# hd6303-mb-ram-rom-x1.net
KiCad netlist of a schematic drawn in EAGLE
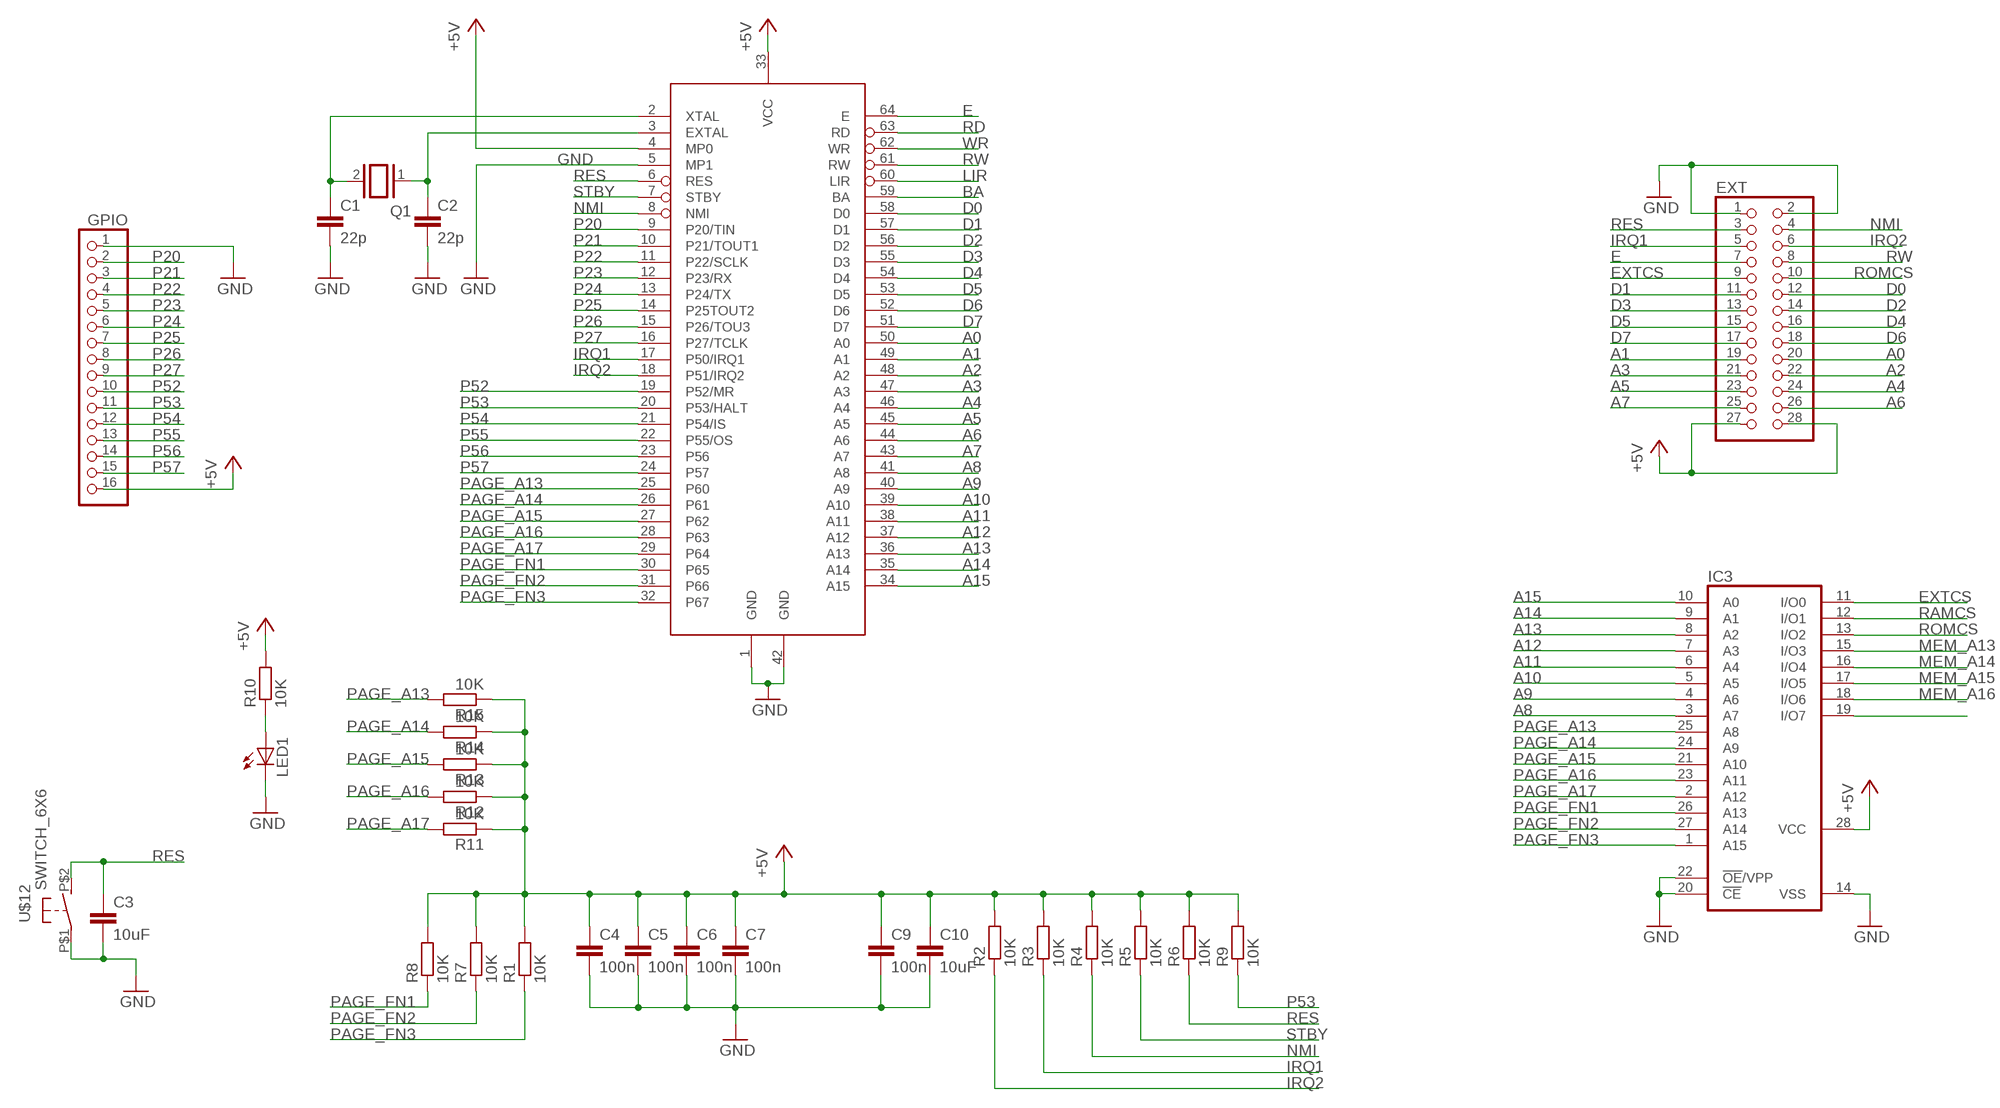
[diagram p0: schematic, sheet 1]
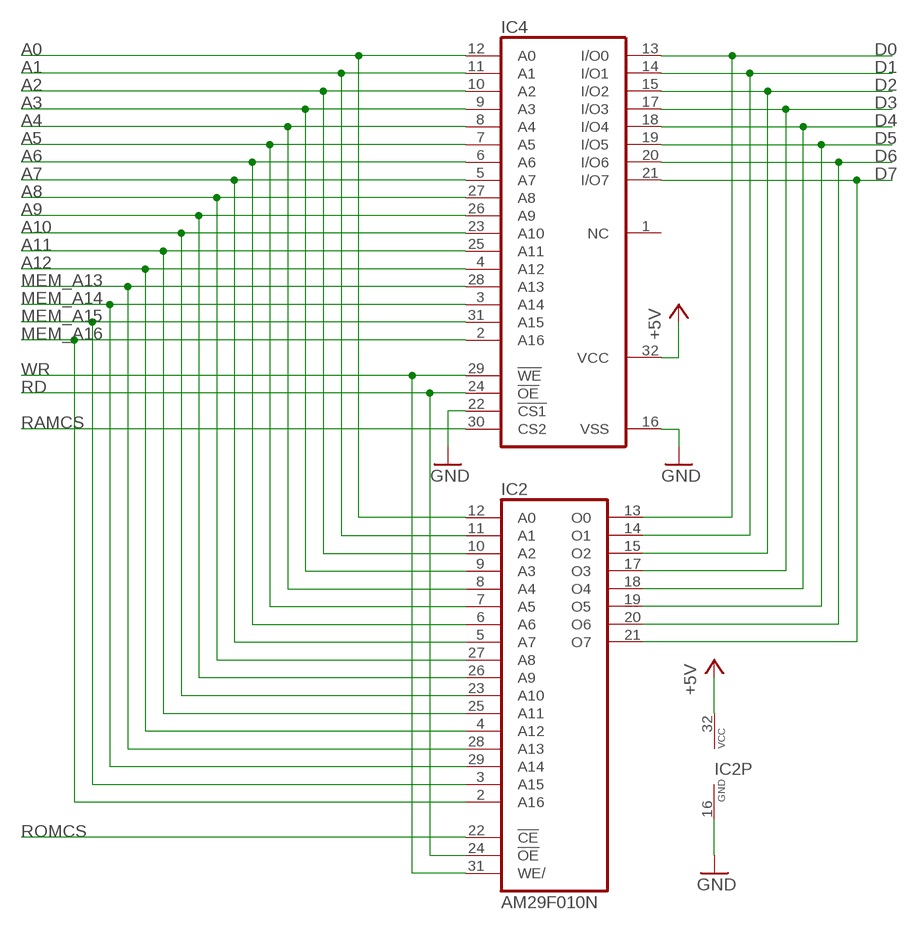
[diagram p1: schematic, sheet 2]

(export (version "E")
  (design (tool "Eeschema 10.0.6"))
  (components
    (comp (ref "C1")
      (value "22p")
      (footprint "eagle-import:C0603")
      (libsource (lib "eagle-import") (part "rcl_334_C-EUC0603"))
    )
    (comp (ref "C2")
      (value "22p")
      (footprint "eagle-import:C0603")
      (libsource (lib "eagle-import") (part "C-EUC0603"))
    )
    (comp (ref "C3")
      (value "10uF")
      (footprint "eagle-import:C0805")
      (libsource (lib "eagle-import") (part "resistor_348_C-EUC0805"))
    )
    (comp (ref "C4")
      (value "100n")
      (footprint "eagle-import:C0603")
      (libsource (lib "eagle-import") (part "C-EUC0603"))
    )
    (comp (ref "C5")
      (value "100n")
      (footprint "eagle-import:C0603")
      (libsource (lib "eagle-import") (part "C-EUC0603"))
    )
    (comp (ref "C6")
      (value "100n")
      (footprint "eagle-import:C0603")
      (libsource (lib "eagle-import") (part "C-EUC0603"))
    )
    (comp (ref "C7")
      (value "100n")
      (footprint "eagle-import:C0603")
      (libsource (lib "eagle-import") (part "C-EUC0603"))
    )
    (comp (ref "C9")
      (value "100n")
      (footprint "eagle-import:C0603")
      (libsource (lib "eagle-import") (part "C-EUC0603"))
    )
    (comp (ref "C10")
      (value "10uF")
      (footprint "eagle-import:C0805")
      (libsource (lib "eagle-import") (part "resistor_348_C-EUC0805"))
    )
    (comp (ref "EXT")
      (value "PINHD-2X14")
      (footprint "eagle-import:2X14")
      (libsource (lib "eagle-import") (part "PINHD-2X14"))
    )
    (comp (ref "GPIO")
      (value "PINHD-1X16")
      (footprint "eagle-import:1X16")
      (libsource (lib "eagle-import") (part "PINHD-1X16"))
    )
    (comp (ref "IC3")
      (value "27512G")
      (footprint "eagle-import:DIL28-6")
      (libsource (lib "eagle-import") (part "27512G"))
    )
    (comp (ref "LED1")
      (value "LED5MM")
      (footprint "eagle-import:LED5MM")
      (libsource (lib "eagle-import") (part "LED5MM"))
    )
    (comp (ref "Q1")
      (value "XTAL/S")
      (footprint "eagle-import:QS")
      (libsource (lib "eagle-import") (part "XTAL/S"))
    )
    (comp (ref "R1")
      (value "10K")
      (footprint "eagle-import:R0603")
      (libsource (lib "eagle-import") (part "R-EU_R0603"))
    )
    (comp (ref "R2")
      (value "10K")
      (footprint "eagle-import:R0603")
      (libsource (lib "eagle-import") (part "R-EU_R0603"))
    )
    (comp (ref "R3")
      (value "10K")
      (footprint "eagle-import:R0603")
      (libsource (lib "eagle-import") (part "R-EU_R0603"))
    )
    (comp (ref "R4")
      (value "10K")
      (footprint "eagle-import:R0603")
      (libsource (lib "eagle-import") (part "R-EU_R0603"))
    )
    (comp (ref "R5")
      (value "10K")
      (footprint "eagle-import:R0603")
      (libsource (lib "eagle-import") (part "R-EU_R0603"))
    )
    (comp (ref "R6")
      (value "10K")
      (footprint "eagle-import:R0603")
      (libsource (lib "eagle-import") (part "R-EU_R0603"))
    )
    (comp (ref "R7")
      (value "10K")
      (footprint "eagle-import:R0603")
      (libsource (lib "eagle-import") (part "R-EU_R0603"))
    )
    (comp (ref "R8")
      (value "10K")
      (footprint "eagle-import:R0603")
      (libsource (lib "eagle-import") (part "R-EU_R0603"))
    )
    (comp (ref "R9")
      (value "10K")
      (footprint "eagle-import:R0603")
      (libsource (lib "eagle-import") (part "R-EU_R0603"))
    )
    (comp (ref "R10")
      (value "10K")
      (footprint "eagle-import:R0603")
      (libsource (lib "eagle-import") (part "R-EU_R0603"))
    )
    (comp (ref "R11")
      (value "10K")
      (footprint "eagle-import:R0603")
      (libsource (lib "eagle-import") (part "R-EU_R0603"))
    )
    (comp (ref "R12")
      (value "10K")
      (footprint "eagle-import:R0603")
      (libsource (lib "eagle-import") (part "R-EU_R0603"))
    )
    (comp (ref "R13")
      (value "10K")
      (footprint "eagle-import:R0603")
      (libsource (lib "eagle-import") (part "R-EU_R0603"))
    )
    (comp (ref "R14")
      (value "10K")
      (footprint "eagle-import:R0603")
      (libsource (lib "eagle-import") (part "R-EU_R0603"))
    )
    (comp (ref "R15")
      (value "10K")
      (footprint "eagle-import:R0603")
      (libsource (lib "eagle-import") (part "R-EU_R0603"))
    )
    (comp (ref "U$1")
      (value "HD6303YCP")
      (footprint "eagle-import:DP-64S")
      (libsource (lib "eagle-import") (part "HD6303YCP"))
    )
    (comp (ref "U$12")
      (value "SWITCH_6X6")
      (footprint "eagle-import:SWITCH_6X6")
      (libsource (lib "eagle-import") (part "SWITCH_6X6"))
    )
    (comp (ref "IC2")
      (value "AM29F010N")
      (footprint "eagle-import:DIP32")
      (libsource (lib "eagle-import") (part "AM29F010N"))
    )
    (comp (ref "IC4")
      (value "628128P")
      (footprint "eagle-import:DIL32")
      (libsource (lib "eagle-import") (part "628128P"))
    )
  )
  (nets
    (net (code "1") (name "+5V") (class "Default")
      (node (ref "C10") (pin "1") (pinfunction "1_1") (pintype "passive"))
      (node (ref "C4") (pin "1") (pinfunction "1_1") (pintype "passive"))
      (node (ref "C5") (pin "1") (pinfunction "1_1") (pintype "passive"))
      (node (ref "C6") (pin "1") (pinfunction "1_1") (pintype "passive"))
      (node (ref "C7") (pin "1") (pinfunction "1_1") (pintype "passive"))
      (node (ref "C9") (pin "1") (pinfunction "1_1") (pintype "passive"))
      (node (ref "EXT") (pin "27") (pinfunction "27_27") (pintype "passive"))
      (node (ref "EXT") (pin "28") (pinfunction "28_28") (pintype "passive"))
      (node (ref "GPIO") (pin "16") (pinfunction "16_16") (pintype "passive"))
      (node (ref "IC2") (pin "32") (pinfunction "VCC_32") (pintype "power_in"))
      (node (ref "IC3") (pin "28") (pinfunction "VCC_28") (pintype "power_in"))
      (node (ref "IC4") (pin "32") (pinfunction "VCC_32") (pintype "power_in"))
      (node (ref "R1") (pin "2") (pinfunction "2_2") (pintype "passive"))
      (node (ref "R10") (pin "2") (pinfunction "2_2") (pintype "passive"))
      (node (ref "R11") (pin "1") (pinfunction "1_1") (pintype "passive"))
      (node (ref "R12") (pin "1") (pinfunction "1_1") (pintype "passive"))
      (node (ref "R13") (pin "1") (pinfunction "1_1") (pintype "passive"))
      (node (ref "R14") (pin "1") (pinfunction "1_1") (pintype "passive"))
      (node (ref "R15") (pin "1") (pinfunction "1_1") (pintype "passive"))
      (node (ref "R2") (pin "2") (pinfunction "2_2") (pintype "passive"))
      (node (ref "R3") (pin "2") (pinfunction "2_2") (pintype "passive"))
      (node (ref "R4") (pin "2") (pinfunction "2_2") (pintype "passive"))
      (node (ref "R5") (pin "2") (pinfunction "2_2") (pintype "passive"))
      (node (ref "R6") (pin "2") (pinfunction "2_2") (pintype "passive"))
      (node (ref "R7") (pin "2") (pinfunction "2_2") (pintype "passive"))
      (node (ref "R8") (pin "2") (pinfunction "2_2") (pintype "passive"))
      (node (ref "R9") (pin "2") (pinfunction "2_2") (pintype "passive"))
      (node (ref "U$1") (pin "33") (pinfunction "VCC_33") (pintype "power_in"))
      (node (ref "U$1") (pin "4") (pinfunction "MP0_4") (pintype "input"))
    )
    (net (code "2") (name "A0") (class "Default")
      (node (ref "EXT") (pin "20") (pinfunction "20_20") (pintype "passive"))
      (node (ref "IC2") (pin "12") (pinfunction "A0_12") (pintype "input"))
      (node (ref "IC4") (pin "12") (pinfunction "A0_12") (pintype "input"))
      (node (ref "U$1") (pin "50") (pinfunction "A0_50") (pintype "output"))
    )
    (net (code "3") (name "A1") (class "Default")
      (node (ref "EXT") (pin "19") (pinfunction "19_19") (pintype "passive"))
      (node (ref "IC2") (pin "11") (pinfunction "A1_11") (pintype "input"))
      (node (ref "IC4") (pin "11") (pinfunction "A1_11") (pintype "input"))
      (node (ref "U$1") (pin "49") (pinfunction "A1_49") (pintype "output"))
    )
    (net (code "4") (name "A2") (class "Default")
      (node (ref "EXT") (pin "22") (pinfunction "22_22") (pintype "passive"))
      (node (ref "IC2") (pin "10") (pinfunction "A2_10") (pintype "input"))
      (node (ref "IC4") (pin "10") (pinfunction "A2_10") (pintype "input"))
      (node (ref "U$1") (pin "48") (pinfunction "A2_48") (pintype "output"))
    )
    (net (code "5") (name "A3") (class "Default")
      (node (ref "EXT") (pin "21") (pinfunction "21_21") (pintype "passive"))
      (node (ref "IC2") (pin "9") (pinfunction "A3_9") (pintype "input"))
      (node (ref "IC4") (pin "9") (pinfunction "A3_9") (pintype "input"))
      (node (ref "U$1") (pin "47") (pinfunction "A3_47") (pintype "output"))
    )
    (net (code "6") (name "A4") (class "Default")
      (node (ref "EXT") (pin "24") (pinfunction "24_24") (pintype "passive"))
      (node (ref "IC2") (pin "8") (pinfunction "A4_8") (pintype "input"))
      (node (ref "IC4") (pin "8") (pinfunction "A4_8") (pintype "input"))
      (node (ref "U$1") (pin "46") (pinfunction "A4_46") (pintype "output"))
    )
    (net (code "7") (name "A5") (class "Default")
      (node (ref "EXT") (pin "23") (pinfunction "23_23") (pintype "passive"))
      (node (ref "IC2") (pin "7") (pinfunction "A5_7") (pintype "input"))
      (node (ref "IC4") (pin "7") (pinfunction "A5_7") (pintype "input"))
      (node (ref "U$1") (pin "45") (pinfunction "A5_45") (pintype "output"))
    )
    (net (code "8") (name "A6") (class "Default")
      (node (ref "EXT") (pin "26") (pinfunction "26_26") (pintype "passive"))
      (node (ref "IC2") (pin "6") (pinfunction "A6_6") (pintype "input"))
      (node (ref "IC4") (pin "6") (pinfunction "A6_6") (pintype "input"))
      (node (ref "U$1") (pin "44") (pinfunction "A6_44") (pintype "output"))
    )
    (net (code "9") (name "A7") (class "Default")
      (node (ref "EXT") (pin "25") (pinfunction "25_25") (pintype "passive"))
      (node (ref "IC2") (pin "5") (pinfunction "A7_5") (pintype "input"))
      (node (ref "IC4") (pin "5") (pinfunction "A7_5") (pintype "input"))
      (node (ref "U$1") (pin "43") (pinfunction "A7_43") (pintype "output"))
    )
    (net (code "10") (name "A8") (class "Default")
      (node (ref "IC2") (pin "27") (pinfunction "A8_27") (pintype "input"))
      (node (ref "IC3") (pin "3") (pinfunction "A7_3") (pintype "input"))
      (node (ref "IC4") (pin "27") (pinfunction "A8_27") (pintype "input"))
      (node (ref "U$1") (pin "41") (pinfunction "A8_41") (pintype "output"))
    )
    (net (code "11") (name "A9") (class "Default")
      (node (ref "IC2") (pin "26") (pinfunction "A9_26") (pintype "input"))
      (node (ref "IC3") (pin "4") (pinfunction "A6_4") (pintype "input"))
      (node (ref "IC4") (pin "26") (pinfunction "A9_26") (pintype "input"))
      (node (ref "U$1") (pin "40") (pinfunction "A9_40") (pintype "output"))
    )
    (net (code "12") (name "A10") (class "Default")
      (node (ref "IC2") (pin "23") (pinfunction "A10_23") (pintype "input"))
      (node (ref "IC3") (pin "5") (pinfunction "A5_5") (pintype "input"))
      (node (ref "IC4") (pin "23") (pinfunction "A10_23") (pintype "input"))
      (node (ref "U$1") (pin "39") (pinfunction "A10_39") (pintype "output"))
    )
    (net (code "13") (name "A11") (class "Default")
      (node (ref "IC2") (pin "25") (pinfunction "A11_25") (pintype "input"))
      (node (ref "IC3") (pin "6") (pinfunction "A4_6") (pintype "input"))
      (node (ref "IC4") (pin "25") (pinfunction "A11_25") (pintype "input"))
      (node (ref "U$1") (pin "38") (pinfunction "A11_38") (pintype "output"))
    )
    (net (code "14") (name "A12") (class "Default")
      (node (ref "IC2") (pin "4") (pinfunction "A12_4") (pintype "input"))
      (node (ref "IC3") (pin "7") (pinfunction "A3_7") (pintype "input"))
      (node (ref "IC4") (pin "4") (pinfunction "A12_4") (pintype "input"))
      (node (ref "U$1") (pin "37") (pinfunction "A12_37") (pintype "output"))
    )
    (net (code "15") (name "A13") (class "Default")
      (node (ref "IC3") (pin "8") (pinfunction "A2_8") (pintype "input"))
      (node (ref "U$1") (pin "36") (pinfunction "A13_36") (pintype "output"))
    )
    (net (code "16") (name "A14") (class "Default")
      (node (ref "IC3") (pin "9") (pinfunction "A1_9") (pintype "input"))
      (node (ref "U$1") (pin "35") (pinfunction "A14_35") (pintype "output"))
    )
    (net (code "17") (name "A15") (class "Default")
      (node (ref "IC3") (pin "10") (pinfunction "A0_10") (pintype "input"))
      (node (ref "U$1") (pin "34") (pinfunction "A15_34") (pintype "output"))
    )
    (net (code "18") (name "BA") (class "Default")
      (node (ref "U$1") (pin "59") (pinfunction "BA_59") (pintype "output"))
    )
    (net (code "19") (name "D0") (class "Default")
      (node (ref "EXT") (pin "12") (pinfunction "12_12") (pintype "passive"))
      (node (ref "IC2") (pin "13") (pinfunction "O0_13") (pintype "tri_state"))
      (node (ref "IC4") (pin "13") (pinfunction "I/O0_13") (pintype "bidirectional"))
      (node (ref "U$1") (pin "58") (pinfunction "D0_58") (pintype "bidirectional"))
    )
    (net (code "20") (name "D1") (class "Default")
      (node (ref "EXT") (pin "11") (pinfunction "11_11") (pintype "passive"))
      (node (ref "IC2") (pin "14") (pinfunction "O1_14") (pintype "tri_state"))
      (node (ref "IC4") (pin "14") (pinfunction "I/O1_14") (pintype "bidirectional"))
      (node (ref "U$1") (pin "57") (pinfunction "D1_57") (pintype "bidirectional"))
    )
    (net (code "21") (name "D2") (class "Default")
      (node (ref "EXT") (pin "14") (pinfunction "14_14") (pintype "passive"))
      (node (ref "IC2") (pin "15") (pinfunction "O2_15") (pintype "tri_state"))
      (node (ref "IC4") (pin "15") (pinfunction "I/O2_15") (pintype "bidirectional"))
      (node (ref "U$1") (pin "56") (pinfunction "D2_56") (pintype "bidirectional"))
    )
    (net (code "22") (name "D3") (class "Default")
      (node (ref "EXT") (pin "13") (pinfunction "13_13") (pintype "passive"))
      (node (ref "IC2") (pin "17") (pinfunction "O3_17") (pintype "tri_state"))
      (node (ref "IC4") (pin "17") (pinfunction "I/O3_17") (pintype "bidirectional"))
      (node (ref "U$1") (pin "55") (pinfunction "D3_55") (pintype "bidirectional"))
    )
    (net (code "23") (name "D4") (class "Default")
      (node (ref "EXT") (pin "16") (pinfunction "16_16") (pintype "passive"))
      (node (ref "IC2") (pin "18") (pinfunction "O4_18") (pintype "tri_state"))
      (node (ref "IC4") (pin "18") (pinfunction "I/O4_18") (pintype "bidirectional"))
      (node (ref "U$1") (pin "54") (pinfunction "D4_54") (pintype "bidirectional"))
    )
    (net (code "24") (name "D5") (class "Default")
      (node (ref "EXT") (pin "15") (pinfunction "15_15") (pintype "passive"))
      (node (ref "IC2") (pin "19") (pinfunction "O5_19") (pintype "tri_state"))
      (node (ref "IC4") (pin "19") (pinfunction "I/O5_19") (pintype "bidirectional"))
      (node (ref "U$1") (pin "53") (pinfunction "D5_53") (pintype "bidirectional"))
    )
    (net (code "25") (name "D6") (class "Default")
      (node (ref "EXT") (pin "18") (pinfunction "18_18") (pintype "passive"))
      (node (ref "IC2") (pin "20") (pinfunction "O6_20") (pintype "tri_state"))
      (node (ref "IC4") (pin "20") (pinfunction "I/O6_20") (pintype "bidirectional"))
      (node (ref "U$1") (pin "52") (pinfunction "D6_52") (pintype "bidirectional"))
    )
    (net (code "26") (name "D7") (class "Default")
      (node (ref "EXT") (pin "17") (pinfunction "17_17") (pintype "passive"))
      (node (ref "IC2") (pin "21") (pinfunction "O7_21") (pintype "tri_state"))
      (node (ref "IC4") (pin "21") (pinfunction "I/O7_21") (pintype "bidirectional"))
      (node (ref "U$1") (pin "51") (pinfunction "D7_51") (pintype "bidirectional"))
    )
    (net (code "27") (name "E") (class "Default")
      (node (ref "EXT") (pin "7") (pinfunction "7_7") (pintype "passive"))
      (node (ref "U$1") (pin "64") (pinfunction "E_64") (pintype "output"))
    )
    (net (code "28") (name "EXTCS") (class "Default")
      (node (ref "EXT") (pin "9") (pinfunction "9_9") (pintype "passive"))
      (node (ref "IC3") (pin "11") (pinfunction "I/O0_11") (pintype "tri_state"))
    )
    (net (code "29") (name "GND") (class "Default")
      (node (ref "C1") (pin "2") (pinfunction "2_2") (pintype "passive"))
      (node (ref "C10") (pin "2") (pinfunction "2_2") (pintype "passive"))
      (node (ref "C2") (pin "2") (pinfunction "2_2") (pintype "passive"))
      (node (ref "C3") (pin "2") (pinfunction "2_2") (pintype "passive"))
      (node (ref "C4") (pin "2") (pinfunction "2_2") (pintype "passive"))
      (node (ref "C5") (pin "2") (pinfunction "2_2") (pintype "passive"))
      (node (ref "C6") (pin "2") (pinfunction "2_2") (pintype "passive"))
      (node (ref "C7") (pin "2") (pinfunction "2_2") (pintype "passive"))
      (node (ref "C9") (pin "2") (pinfunction "2_2") (pintype "passive"))
      (node (ref "EXT") (pin "1") (pinfunction "1_1") (pintype "passive"))
      (node (ref "EXT") (pin "2") (pinfunction "2_2") (pintype "passive"))
      (node (ref "GPIO") (pin "1") (pinfunction "1_1") (pintype "passive"))
      (node (ref "IC2") (pin "16") (pinfunction "GND_16") (pintype "power_in"))
      (node (ref "IC3") (pin "14") (pinfunction "VSS_14") (pintype "power_in"))
      (node (ref "IC3") (pin "20") (pinfunction "~{CE}_20") (pintype "input"))
      (node (ref "IC3") (pin "22") (pinfunction "~{OE}/VPP_22") (pintype "input"))
      (node (ref "IC4") (pin "16") (pinfunction "VSS_16") (pintype "power_in"))
      (node (ref "IC4") (pin "22") (pinfunction "~{CS1}_22") (pintype "input"))
      (node (ref "LED1") (pin "K") (pinfunction "C_K") (pintype "passive"))
      (node (ref "U$1") (pin "1") (pinfunction "GND_1") (pintype "power_in"))
      (node (ref "U$1") (pin "42") (pinfunction "GND_42") (pintype "power_in"))
      (node (ref "U$1") (pin "5") (pinfunction "MP1_5") (pintype "input"))
      (node (ref "U$12") (pin "P$1") (pinfunction "P_P$1") (pintype "passive"))
    )
    (net (code "30") (name "IRQ1") (class "Default")
      (node (ref "EXT") (pin "5") (pinfunction "5_5") (pintype "passive"))
      (node (ref "R3") (pin "1") (pinfunction "1_1") (pintype "passive"))
      (node (ref "U$1") (pin "17") (pinfunction "P50/IRQ1_17") (pintype "bidirectional"))
    )
    (net (code "31") (name "IRQ2") (class "Default")
      (node (ref "EXT") (pin "6") (pinfunction "6_6") (pintype "passive"))
      (node (ref "R2") (pin "1") (pinfunction "1_1") (pintype "passive"))
      (node (ref "U$1") (pin "18") (pinfunction "P51/IRQ2_18") (pintype "bidirectional"))
    )
    (net (code "32") (name "LIR") (class "Default")
      (node (ref "U$1") (pin "60") (pinfunction "LIR_60") (pintype "output"))
    )
    (net (code "33") (name "MEM_A13") (class "Default")
      (node (ref "IC2") (pin "28") (pinfunction "A13_28") (pintype "input"))
      (node (ref "IC3") (pin "15") (pinfunction "I/O3_15") (pintype "tri_state"))
      (node (ref "IC4") (pin "28") (pinfunction "A13_28") (pintype "input"))
    )
    (net (code "34") (name "MEM_A14") (class "Default")
      (node (ref "IC2") (pin "29") (pinfunction "A14_29") (pintype "input"))
      (node (ref "IC3") (pin "16") (pinfunction "I/O4_16") (pintype "tri_state"))
      (node (ref "IC4") (pin "3") (pinfunction "A14_3") (pintype "input"))
    )
    (net (code "35") (name "MEM_A15") (class "Default")
      (node (ref "IC2") (pin "3") (pinfunction "A15_3") (pintype "input"))
      (node (ref "IC3") (pin "17") (pinfunction "I/O5_17") (pintype "tri_state"))
      (node (ref "IC4") (pin "31") (pinfunction "A15_31") (pintype "input"))
    )
    (net (code "36") (name "MEM_A16") (class "Default")
      (node (ref "IC2") (pin "2") (pinfunction "A16_2") (pintype "input"))
      (node (ref "IC3") (pin "18") (pinfunction "I/O6_18") (pintype "tri_state"))
      (node (ref "IC4") (pin "2") (pinfunction "A16_2") (pintype "input"))
    )
    (net (code "37") (name "NMI") (class "Default")
      (node (ref "EXT") (pin "4") (pinfunction "4_4") (pintype "passive"))
      (node (ref "R4") (pin "1") (pinfunction "1_1") (pintype "passive"))
      (node (ref "U$1") (pin "8") (pinfunction "NMI_8") (pintype "input"))
    )
    (net (code "38") (name "Net-(LED1-PadA)") (class "Default")
      (node (ref "LED1") (pin "A") (pinfunction "A_A") (pintype "passive"))
      (node (ref "R10") (pin "1") (pinfunction "1_1") (pintype "passive"))
    )
    (net (code "39") (name "Net-(U$1-EXTAL)") (class "Default")
      (node (ref "C2") (pin "1") (pinfunction "1_1") (pintype "passive"))
      (node (ref "Q1") (pin "1") (pinfunction "1_1") (pintype "passive"))
      (node (ref "U$1") (pin "3") (pinfunction "EXTAL_3") (pintype "input"))
    )
    (net (code "40") (name "Net-(U$1-XTAL)") (class "Default")
      (node (ref "C1") (pin "1") (pinfunction "1_1") (pintype "passive"))
      (node (ref "Q1") (pin "2") (pinfunction "2_2") (pintype "passive"))
      (node (ref "U$1") (pin "2") (pinfunction "XTAL_2") (pintype "input"))
    )
    (net (code "41") (name "P20") (class "Default")
      (node (ref "GPIO") (pin "2") (pinfunction "2_2") (pintype "passive"))
      (node (ref "U$1") (pin "9") (pinfunction "P20/TIN_9") (pintype "bidirectional"))
    )
    (net (code "42") (name "P21") (class "Default")
      (node (ref "GPIO") (pin "3") (pinfunction "3_3") (pintype "passive"))
      (node (ref "U$1") (pin "10") (pinfunction "P21/TOUT1_10") (pintype "bidirectional"))
    )
    (net (code "43") (name "P22") (class "Default")
      (node (ref "GPIO") (pin "4") (pinfunction "4_4") (pintype "passive"))
      (node (ref "U$1") (pin "11") (pinfunction "P22/SCLK_11") (pintype "bidirectional"))
    )
    (net (code "44") (name "P23") (class "Default")
      (node (ref "GPIO") (pin "5") (pinfunction "5_5") (pintype "passive"))
      (node (ref "U$1") (pin "12") (pinfunction "P23/RX_12") (pintype "bidirectional"))
    )
    (net (code "45") (name "P24") (class "Default")
      (node (ref "GPIO") (pin "6") (pinfunction "6_6") (pintype "passive"))
      (node (ref "U$1") (pin "13") (pinfunction "P24/TX_13") (pintype "bidirectional"))
    )
    (net (code "46") (name "P25") (class "Default")
      (node (ref "GPIO") (pin "7") (pinfunction "7_7") (pintype "passive"))
      (node (ref "U$1") (pin "14") (pinfunction "P25TOUT2_14") (pintype "bidirectional"))
    )
    (net (code "47") (name "P26") (class "Default")
      (node (ref "GPIO") (pin "8") (pinfunction "8_8") (pintype "passive"))
      (node (ref "U$1") (pin "15") (pinfunction "P26/TOU3_15") (pintype "bidirectional"))
    )
    (net (code "48") (name "P27") (class "Default")
      (node (ref "GPIO") (pin "9") (pinfunction "9_9") (pintype "passive"))
      (node (ref "U$1") (pin "16") (pinfunction "P27/TCLK_16") (pintype "bidirectional"))
    )
    (net (code "49") (name "P52") (class "Default")
      (node (ref "GPIO") (pin "10") (pinfunction "10_10") (pintype "passive"))
      (node (ref "U$1") (pin "19") (pinfunction "P52/MR_19") (pintype "bidirectional"))
    )
    (net (code "50") (name "P53") (class "Default")
      (node (ref "GPIO") (pin "11") (pinfunction "11_11") (pintype "passive"))
      (node (ref "R9") (pin "1") (pinfunction "1_1") (pintype "passive"))
      (node (ref "U$1") (pin "20") (pinfunction "P53/HALT_20") (pintype "bidirectional"))
    )
    (net (code "51") (name "P54") (class "Default")
      (node (ref "GPIO") (pin "12") (pinfunction "12_12") (pintype "passive"))
      (node (ref "U$1") (pin "21") (pinfunction "P54/IS_21") (pintype "bidirectional"))
    )
    (net (code "52") (name "P55") (class "Default")
      (node (ref "GPIO") (pin "13") (pinfunction "13_13") (pintype "passive"))
      (node (ref "U$1") (pin "22") (pinfunction "P55/OS_22") (pintype "bidirectional"))
    )
    (net (code "53") (name "P56") (class "Default")
      (node (ref "GPIO") (pin "14") (pinfunction "14_14") (pintype "passive"))
      (node (ref "U$1") (pin "23") (pinfunction "P56_23") (pintype "bidirectional"))
    )
    (net (code "54") (name "P57") (class "Default")
      (node (ref "GPIO") (pin "15") (pinfunction "15_15") (pintype "passive"))
      (node (ref "U$1") (pin "24") (pinfunction "P57_24") (pintype "bidirectional"))
    )
    (net (code "55") (name "PAGE_A13") (class "Default")
      (node (ref "IC3") (pin "25") (pinfunction "A8_25") (pintype "input"))
      (node (ref "R15") (pin "2") (pinfunction "2_2") (pintype "passive"))
      (node (ref "U$1") (pin "25") (pinfunction "P60_25") (pintype "bidirectional"))
    )
    (net (code "56") (name "PAGE_A14") (class "Default")
      (node (ref "IC3") (pin "24") (pinfunction "A9_24") (pintype "input"))
      (node (ref "R14") (pin "2") (pinfunction "2_2") (pintype "passive"))
      (node (ref "U$1") (pin "26") (pinfunction "P61_26") (pintype "bidirectional"))
    )
    (net (code "57") (name "PAGE_A15") (class "Default")
      (node (ref "IC3") (pin "21") (pinfunction "A10_21") (pintype "input"))
      (node (ref "R13") (pin "2") (pinfunction "2_2") (pintype "passive"))
      (node (ref "U$1") (pin "27") (pinfunction "P62_27") (pintype "bidirectional"))
    )
    (net (code "58") (name "PAGE_A16") (class "Default")
      (node (ref "IC3") (pin "23") (pinfunction "A11_23") (pintype "input"))
      (node (ref "R12") (pin "2") (pinfunction "2_2") (pintype "passive"))
      (node (ref "U$1") (pin "28") (pinfunction "P63_28") (pintype "bidirectional"))
    )
    (net (code "59") (name "PAGE_A17") (class "Default")
      (node (ref "IC3") (pin "2") (pinfunction "A12_2") (pintype "input"))
      (node (ref "R11") (pin "2") (pinfunction "2_2") (pintype "passive"))
      (node (ref "U$1") (pin "29") (pinfunction "P64_29") (pintype "bidirectional"))
    )
    (net (code "60") (name "PAGE_FN1") (class "Default")
      (node (ref "IC3") (pin "26") (pinfunction "A13_26") (pintype "input"))
      (node (ref "R8") (pin "1") (pinfunction "1_1") (pintype "passive"))
      (node (ref "U$1") (pin "30") (pinfunction "P65_30") (pintype "bidirectional"))
    )
    (net (code "61") (name "PAGE_FN2") (class "Default")
      (node (ref "IC3") (pin "27") (pinfunction "A14_27") (pintype "input"))
      (node (ref "R7") (pin "1") (pinfunction "1_1") (pintype "passive"))
      (node (ref "U$1") (pin "31") (pinfunction "P66_31") (pintype "bidirectional"))
    )
    (net (code "62") (name "PAGE_FN3") (class "Default")
      (node (ref "IC3") (pin "1") (pinfunction "A15_1") (pintype "input"))
      (node (ref "R1") (pin "1") (pinfunction "1_1") (pintype "passive"))
      (node (ref "U$1") (pin "32") (pinfunction "P67_32") (pintype "bidirectional"))
    )
    (net (code "63") (name "RAMCS") (class "Default")
      (node (ref "IC3") (pin "12") (pinfunction "I/O1_12") (pintype "tri_state"))
      (node (ref "IC4") (pin "30") (pinfunction "CS2_30") (pintype "input"))
    )
    (net (code "64") (name "RD") (class "Default")
      (node (ref "IC2") (pin "24") (pinfunction "~{OE}_24") (pintype "input"))
      (node (ref "IC4") (pin "24") (pinfunction "~{OE}_24") (pintype "input"))
      (node (ref "U$1") (pin "63") (pinfunction "RD_63") (pintype "output"))
    )
    (net (code "65") (name "RES") (class "Default")
      (node (ref "C3") (pin "1") (pinfunction "1_1") (pintype "passive"))
      (node (ref "EXT") (pin "3") (pinfunction "3_3") (pintype "passive"))
      (node (ref "R6") (pin "1") (pinfunction "1_1") (pintype "passive"))
      (node (ref "U$1") (pin "6") (pinfunction "RES_6") (pintype "input"))
      (node (ref "U$12") (pin "P$2") (pinfunction "S_P$2") (pintype "passive"))
    )
    (net (code "66") (name "ROMCS") (class "Default")
      (node (ref "EXT") (pin "10") (pinfunction "10_10") (pintype "passive"))
      (node (ref "IC2") (pin "22") (pinfunction "~{CE}_22") (pintype "input"))
      (node (ref "IC3") (pin "13") (pinfunction "I/O2_13") (pintype "tri_state"))
    )
    (net (code "67") (name "RW") (class "Default")
      (node (ref "EXT") (pin "8") (pinfunction "8_8") (pintype "passive"))
      (node (ref "U$1") (pin "61") (pinfunction "RW_61") (pintype "output"))
    )
    (net (code "68") (name "STBY") (class "Default")
      (node (ref "R5") (pin "1") (pinfunction "1_1") (pintype "passive"))
      (node (ref "U$1") (pin "7") (pinfunction "STBY_7") (pintype "input"))
    )
    (net (code "69") (name "WR") (class "Default")
      (node (ref "IC2") (pin "31") (pinfunction "WE/_31") (pintype "input"))
      (node (ref "IC4") (pin "29") (pinfunction "~{WE}_29") (pintype "input"))
      (node (ref "U$1") (pin "62") (pinfunction "WR_62") (pintype "output"))
    )
    (net (code "70") (name "unconnected-(IC3-I{slash}O7-Pad19)") (class "Default")
      (node (ref "IC3") (pin "19") (pinfunction "I/O7_19") (pintype "tri_state"))
    )
    (net (code "71") (name "unconnected-(IC4-NC-Pad1)") (class "Default")
      (node (ref "IC4") (pin "1") (pinfunction "NC_1") (pintype "no_connect"))
    )
  )
)
